# IO_ctrl.net
KiCad netlist of a schematic drawn in Altium Designer
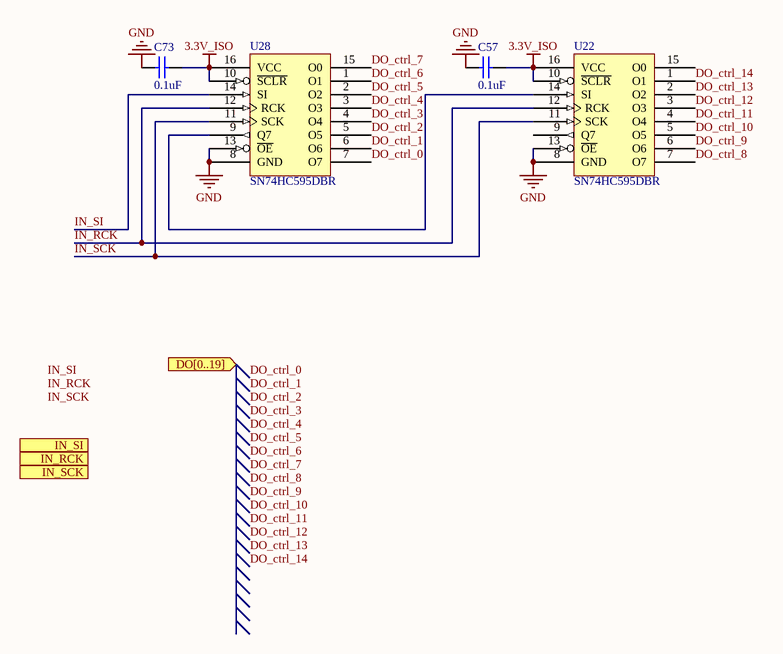
[diagram p0: IO_ctrl.SchDoc]

(export (version "E")
  (design (tool "Eeschema 10.0.6"))
  (components
    (comp (ref "C57")
      (value "0.1uF")
      (footprint "0603C")
      (description "Capacitor")
      (fields (field (name "PUBLISHER") "Altium Limited"))
      (libsource (lib "Miscellaneous Devices") (part "Cap"))
    )
    (comp (ref "C73")
      (value "0.1uF")
      (footprint "0603C")
      (description "Capacitor")
      (fields (field (name "PUBLISHER") "Altium Limited"))
      (libsource (lib "Miscellaneous Devices") (part "Cap"))
    )
    (comp (ref "U22") (value "SN74HC595DBR") (footprint "SSOP16") (libsource (lib "DI16") (part "74HC595")))
    (comp (ref "U28") (value "SN74HC595DBR") (footprint "SSOP16") (libsource (lib "DI16") (part "74HC595")))
  )
  (nets
    (net (code "22") (name "/DO_ctrl_0") (class "Default")
      (node (ref "U28") (pin "7") (pinfunction "O7_7") (pintype "tri_state"))
    )
    (net (code "23") (name "/DO_ctrl_1") (class "Default")
      (node (ref "U28") (pin "6") (pinfunction "O6_6") (pintype "tri_state"))
    )
    (net (code "24") (name "/DO_ctrl_2") (class "Default")
      (node (ref "U28") (pin "5") (pinfunction "O5_5") (pintype "tri_state"))
    )
    (net (code "25") (name "/DO_ctrl_3") (class "Default")
      (node (ref "U28") (pin "4") (pinfunction "O4_4") (pintype "tri_state"))
    )
    (net (code "26") (name "/DO_ctrl_4") (class "Default")
      (node (ref "U28") (pin "3") (pinfunction "O3_3") (pintype "tri_state"))
    )
    (net (code "27") (name "/DO_ctrl_5") (class "Default")
      (node (ref "U28") (pin "2") (pinfunction "O2_2") (pintype "tri_state"))
    )
    (net (code "28") (name "/DO_ctrl_6") (class "Default")
      (node (ref "U28") (pin "1") (pinfunction "O1_1") (pintype "tri_state"))
    )
    (net (code "29") (name "/DO_ctrl_7") (class "Default")
      (node (ref "U28") (pin "15") (pinfunction "O0_15") (pintype "tri_state"))
    )
    (net (code "30") (name "/DO_ctrl_8") (class "Default")
      (node (ref "U22") (pin "7") (pinfunction "O7_7") (pintype "tri_state"))
    )
    (net (code "31") (name "/DO_ctrl_9") (class "Default")
      (node (ref "U22") (pin "6") (pinfunction "O6_6") (pintype "tri_state"))
    )
    (net (code "32") (name "/DO_ctrl_10") (class "Default")
      (node (ref "U22") (pin "5") (pinfunction "O5_5") (pintype "tri_state"))
    )
    (net (code "33") (name "/DO_ctrl_11") (class "Default")
      (node (ref "U22") (pin "4") (pinfunction "O4_4") (pintype "tri_state"))
    )
    (net (code "34") (name "/DO_ctrl_12") (class "Default")
      (node (ref "U22") (pin "3") (pinfunction "O3_3") (pintype "tri_state"))
    )
    (net (code "35") (name "/DO_ctrl_13") (class "Default")
      (node (ref "U22") (pin "2") (pinfunction "O2_2") (pintype "tri_state"))
    )
    (net (code "36") (name "/DO_ctrl_14") (class "Default")
      (node (ref "U22") (pin "1") (pinfunction "O1_1") (pintype "tri_state"))
    )
    (net (code "37") (name "/IN_RCK") (class "Default")
      (node (ref "U22") (pin "12") (pinfunction "RCK_12") (pintype "input"))
      (node (ref "U28") (pin "12") (pinfunction "RCK_12") (pintype "input"))
    )
    (net (code "38") (name "/IN_SCK") (class "Default")
      (node (ref "U22") (pin "11") (pinfunction "SCK_11") (pintype "input"))
      (node (ref "U28") (pin "11") (pinfunction "SCK_11") (pintype "input"))
    )
    (net (code "39") (name "/IN_SI") (class "Default")
      (node (ref "U28") (pin "14") (pinfunction "SI_14") (pintype "input"))
    )
    (net (code "40") (name "3.3V_ISO") (class "Default")
      (node (ref "C57") (pin "1") (pinfunction "1_1") (pintype "passive"))
      (node (ref "C73") (pin "1") (pinfunction "1_1") (pintype "passive"))
      (node (ref "U22") (pin "10") (pinfunction "~{SCLR}_10") (pintype "input"))
      (node (ref "U22") (pin "16") (pinfunction "VCC_16") (pintype "power_in"))
      (node (ref "U28") (pin "10") (pinfunction "~{SCLR}_10") (pintype "input"))
      (node (ref "U28") (pin "16") (pinfunction "VCC_16") (pintype "power_in"))
    )
    (net (code "41") (name "GND") (class "Default")
      (node (ref "C57") (pin "2") (pinfunction "2_2") (pintype "passive"))
      (node (ref "C73") (pin "2") (pinfunction "2_2") (pintype "passive"))
      (node (ref "U22") (pin "13") (pinfunction "~{OE}_13") (pintype "input"))
      (node (ref "U22") (pin "8") (pinfunction "GND_8") (pintype "power_in"))
      (node (ref "U28") (pin "13") (pinfunction "~{OE}_13") (pintype "input"))
      (node (ref "U28") (pin "8") (pinfunction "GND_8") (pintype "power_in"))
    )
    (net (code "42") (name "Net-(U22-SI)") (class "Default")
      (node (ref "U22") (pin "14") (pinfunction "SI_14") (pintype "input"))
      (node (ref "U28") (pin "9") (pinfunction "Q7_9") (pintype "output"))
    )
    (net (code "43") (name "unconnected-(U22-O0-Pad15)") (class "Default")
      (node (ref "U22") (pin "15") (pinfunction "O0_15") (pintype "tri_state"))
    )
    (net (code "44") (name "unconnected-(U22-Q7-Pad9)") (class "Default")
      (node (ref "U22") (pin "9") (pinfunction "Q7_9") (pintype "output"))
    )
  )
)
